# TriDeer.net
KiCad netlist of a schematic drawn in Altium Designer
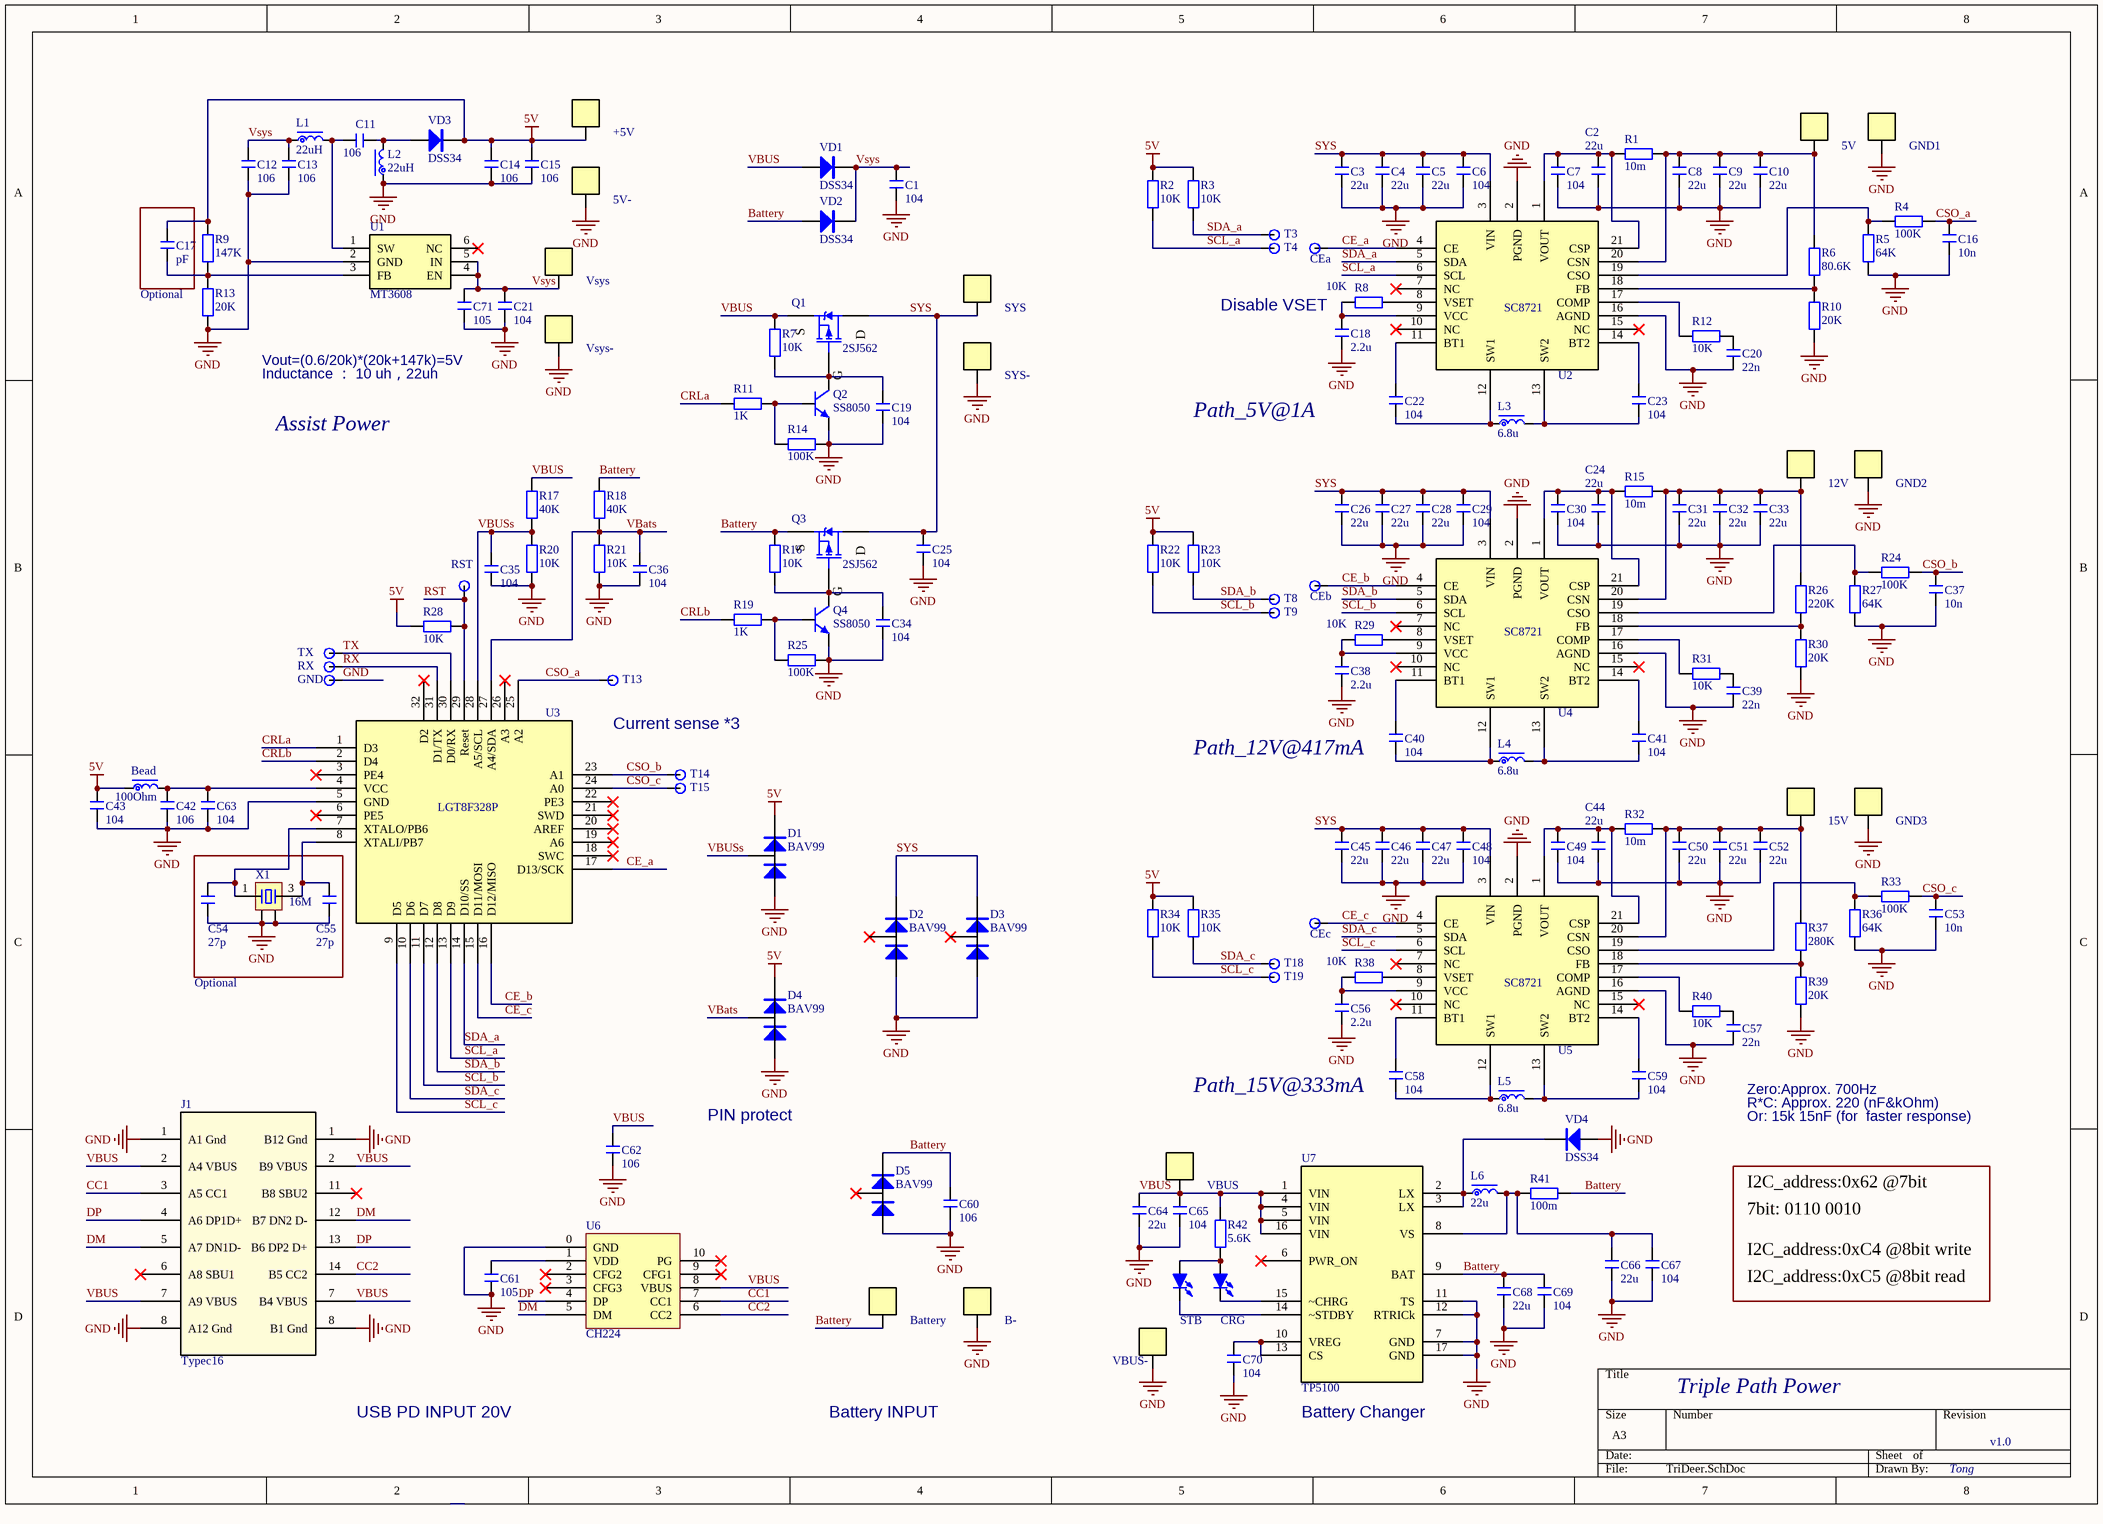
[diagram p0: TriDeer.SchDoc]

(export (version "E")
  (design (tool "Eeschema 10.0.6"))
  (components
    (comp (ref "+5V") (value "1") (footprint "connect") (libsource (lib "A") (part "connect")))
    (comp (ref "5V") (value "1") (footprint "connect") (libsource (lib "A") (part "connect")))
    (comp (ref "5V-") (value "1") (footprint "connect") (libsource (lib "A") (part "connect")))
    (comp (ref "12V") (value "1") (footprint "connect") (libsource (lib "A") (part "connect")))
    (comp (ref "15V") (value "1") (footprint "connect") (libsource (lib "A") (part "connect")))
    (comp (ref "B-") (value "1") (footprint "connect") (libsource (lib "A") (part "connect")))
    (comp (ref "Battery") (value "1") (footprint "connect") (libsource (lib "A") (part "connect")))
    (comp (ref "Bead")
      (value "100Ohm")
      (footprint "L 0805")
      (description "BEAD")
      (libsource (lib "A") (part "BEAD"))
    )
    (comp (ref "C1")
      (value "104")
      (footprint "C 0603")
      (description "瓷片电容-贴片")
      (libsource (lib "A") (part "Cap-CER-SMD_1"))
    )
    (comp (ref "C2")
      (value "22u")
      (footprint "C 0805")
      (description "瓷片电容-贴片")
      (libsource (lib "A") (part "Cap-CER-SMD_1"))
    )
    (comp (ref "C3")
      (value "22u")
      (footprint "C 0805")
      (description "瓷片电容-贴片")
      (libsource (lib "A") (part "Cap-CER-SMD_1"))
    )
    (comp (ref "C4")
      (value "22u")
      (footprint "C 0805")
      (description "瓷片电容-贴片")
      (libsource (lib "A") (part "Cap-CER-SMD_1"))
    )
    (comp (ref "C5")
      (value "22u")
      (footprint "C 0805")
      (description "瓷片电容-贴片")
      (libsource (lib "A") (part "Cap-CER-SMD_1"))
    )
    (comp (ref "C6")
      (value "104")
      (footprint "C 0603")
      (description "瓷片电容-贴片")
      (libsource (lib "A") (part "Cap-CER-SMD_1"))
    )
    (comp (ref "C7")
      (value "104")
      (footprint "C 0603")
      (description "瓷片电容-贴片")
      (libsource (lib "A") (part "Cap-CER-SMD_1"))
    )
    (comp (ref "C8")
      (value "22u")
      (footprint "C 0805")
      (description "瓷片电容-贴片")
      (libsource (lib "A") (part "Cap-CER-SMD_1"))
    )
    (comp (ref "C9")
      (value "22u")
      (footprint "C 0805")
      (description "瓷片电容-贴片")
      (libsource (lib "A") (part "Cap-CER-SMD_1"))
    )
    (comp (ref "C10")
      (value "22u")
      (footprint "C 0805")
      (description "瓷片电容-贴片")
      (libsource (lib "A") (part "Cap-CER-SMD_1"))
    )
    (comp (ref "C11")
      (value "106")
      (footprint "C 0805")
      (description "瓷片电容-贴片")
      (libsource (lib "A") (part "Cap-CER-SMD_1"))
    )
    (comp (ref "C12")
      (value "106")
      (footprint "C 0805")
      (description "瓷片电容-贴片")
      (libsource (lib "A") (part "Cap-CER-SMD_1"))
    )
    (comp (ref "C13")
      (value "106")
      (footprint "C 0805")
      (description "瓷片电容-贴片")
      (libsource (lib "A") (part "Cap-CER-SMD_1"))
    )
    (comp (ref "C14")
      (value "106")
      (footprint "C 0805")
      (description "瓷片电容-贴片")
      (libsource (lib "A") (part "Cap-CER-SMD_1"))
    )
    (comp (ref "C15")
      (value "106")
      (footprint "C 0805")
      (description "瓷片电容-贴片")
      (libsource (lib "A") (part "Cap-CER-SMD_1"))
    )
    (comp (ref "C16")
      (value "10n")
      (footprint "C 0603")
      (description "瓷片电容-贴片")
      (libsource (lib "A") (part "Cap-CER-SMD_1"))
    )
    (comp (ref "C17")
      (value "pF")
      (footprint "C 0603")
      (description "瓷片电容-贴片")
      (libsource (lib "A") (part "Cap-CER-SMD_1"))
    )
    (comp (ref "C18")
      (value "2.2u")
      (footprint "C 0603")
      (description "瓷片电容-贴片")
      (libsource (lib "A") (part "Cap-CER-SMD_1"))
    )
    (comp (ref "C19")
      (value "104")
      (footprint "C 0603")
      (description "瓷片电容-贴片")
      (libsource (lib "A") (part "Cap-CER-SMD_1"))
    )
    (comp (ref "C20")
      (value "22n")
      (footprint "C 0603")
      (description "瓷片电容-贴片")
      (libsource (lib "A") (part "Cap-CER-SMD_1"))
    )
    (comp (ref "C21")
      (value "104")
      (footprint "C 0603")
      (description "瓷片电容-贴片")
      (libsource (lib "A") (part "Cap-CER-SMD_1"))
    )
    (comp (ref "C22")
      (value "104")
      (footprint "C 0603")
      (description "瓷片电容-贴片")
      (libsource (lib "A") (part "Cap-CER-SMD_1"))
    )
    (comp (ref "C23")
      (value "104")
      (footprint "C 0603")
      (description "瓷片电容-贴片")
      (libsource (lib "A") (part "Cap-CER-SMD_1"))
    )
    (comp (ref "C24")
      (value "22u")
      (footprint "C 0805")
      (description "瓷片电容-贴片")
      (libsource (lib "A") (part "Cap-CER-SMD_1"))
    )
    (comp (ref "C25")
      (value "104")
      (footprint "C 0603")
      (description "瓷片电容-贴片")
      (libsource (lib "A") (part "Cap-CER-SMD_1"))
    )
    (comp (ref "C26")
      (value "22u")
      (footprint "C 0805")
      (description "瓷片电容-贴片")
      (libsource (lib "A") (part "Cap-CER-SMD_1"))
    )
    (comp (ref "C27")
      (value "22u")
      (footprint "C 0805")
      (description "瓷片电容-贴片")
      (libsource (lib "A") (part "Cap-CER-SMD_1"))
    )
    (comp (ref "C28")
      (value "22u")
      (footprint "C 0805")
      (description "瓷片电容-贴片")
      (libsource (lib "A") (part "Cap-CER-SMD_1"))
    )
    (comp (ref "C29")
      (value "104")
      (footprint "C 0603")
      (description "瓷片电容-贴片")
      (libsource (lib "A") (part "Cap-CER-SMD_1"))
    )
    (comp (ref "C30")
      (value "104")
      (footprint "C 0603")
      (description "瓷片电容-贴片")
      (libsource (lib "A") (part "Cap-CER-SMD_1"))
    )
    (comp (ref "C31")
      (value "22u")
      (footprint "C 0805")
      (description "瓷片电容-贴片")
      (libsource (lib "A") (part "Cap-CER-SMD_1"))
    )
    (comp (ref "C32")
      (value "22u")
      (footprint "C 0805")
      (description "瓷片电容-贴片")
      (libsource (lib "A") (part "Cap-CER-SMD_1"))
    )
    (comp (ref "C33")
      (value "22u")
      (footprint "C 0805")
      (description "瓷片电容-贴片")
      (libsource (lib "A") (part "Cap-CER-SMD_1"))
    )
    (comp (ref "C34")
      (value "104")
      (footprint "C 0603")
      (description "瓷片电容-贴片")
      (libsource (lib "A") (part "Cap-CER-SMD_1"))
    )
    (comp (ref "C35")
      (value "104")
      (footprint "C 0603")
      (description "瓷片电容-贴片")
      (libsource (lib "A") (part "Cap-CER-SMD_1"))
    )
    (comp (ref "C36")
      (value "104")
      (footprint "C 0603")
      (description "瓷片电容-贴片")
      (libsource (lib "A") (part "Cap-CER-SMD_1"))
    )
    (comp (ref "C37")
      (value "10n")
      (footprint "C 0603")
      (description "瓷片电容-贴片")
      (libsource (lib "A") (part "Cap-CER-SMD_1"))
    )
    (comp (ref "C38")
      (value "2.2u")
      (footprint "C 0603")
      (description "瓷片电容-贴片")
      (libsource (lib "A") (part "Cap-CER-SMD_1"))
    )
    (comp (ref "C39")
      (value "22n")
      (footprint "C 0603")
      (description "瓷片电容-贴片")
      (libsource (lib "A") (part "Cap-CER-SMD_1"))
    )
    (comp (ref "C40")
      (value "104")
      (footprint "C 0603")
      (description "瓷片电容-贴片")
      (libsource (lib "A") (part "Cap-CER-SMD_1"))
    )
    (comp (ref "C41")
      (value "104")
      (footprint "C 0603")
      (description "瓷片电容-贴片")
      (libsource (lib "A") (part "Cap-CER-SMD_1"))
    )
    (comp (ref "C42")
      (value "106")
      (footprint "C 0805")
      (description "瓷片电容-贴片")
      (libsource (lib "A") (part "Cap-CER-SMD_1"))
    )
    (comp (ref "C43")
      (value "104")
      (footprint "C 0603")
      (description "瓷片电容-贴片")
      (libsource (lib "A") (part "Cap-CER-SMD_1"))
    )
    (comp (ref "C44")
      (value "22u")
      (footprint "C 0805")
      (description "瓷片电容-贴片")
      (libsource (lib "A") (part "Cap-CER-SMD_1"))
    )
    (comp (ref "C45")
      (value "22u")
      (footprint "C 0805")
      (description "瓷片电容-贴片")
      (libsource (lib "A") (part "Cap-CER-SMD_1"))
    )
    (comp (ref "C46")
      (value "22u")
      (footprint "C 0805")
      (description "瓷片电容-贴片")
      (libsource (lib "A") (part "Cap-CER-SMD_1"))
    )
    (comp (ref "C47")
      (value "22u")
      (footprint "C 0805")
      (description "瓷片电容-贴片")
      (libsource (lib "A") (part "Cap-CER-SMD_1"))
    )
    (comp (ref "C48")
      (value "104")
      (footprint "C 0603")
      (description "瓷片电容-贴片")
      (libsource (lib "A") (part "Cap-CER-SMD_1"))
    )
    (comp (ref "C49")
      (value "104")
      (footprint "C 0603")
      (description "瓷片电容-贴片")
      (libsource (lib "A") (part "Cap-CER-SMD_1"))
    )
    (comp (ref "C50")
      (value "22u")
      (footprint "C 0805")
      (description "瓷片电容-贴片")
      (libsource (lib "A") (part "Cap-CER-SMD_1"))
    )
    (comp (ref "C51")
      (value "22u")
      (footprint "C 0805")
      (description "瓷片电容-贴片")
      (libsource (lib "A") (part "Cap-CER-SMD_1"))
    )
    (comp (ref "C52")
      (value "22u")
      (footprint "C 0805")
      (description "瓷片电容-贴片")
      (libsource (lib "A") (part "Cap-CER-SMD_1"))
    )
    (comp (ref "C53")
      (value "10n")
      (footprint "C 0603")
      (description "瓷片电容-贴片")
      (libsource (lib "A") (part "Cap-CER-SMD_1"))
    )
    (comp (ref "C54")
      (value "27p")
      (footprint "C 0603")
      (description "瓷片电容-贴片")
      (libsource (lib "A") (part "Cap-CER-SMD_1"))
    )
    (comp (ref "C55")
      (value "27p")
      (footprint "C 0603")
      (description "瓷片电容-贴片")
      (libsource (lib "A") (part "Cap-CER-SMD_1"))
    )
    (comp (ref "C56")
      (value "2.2u")
      (footprint "C 0603")
      (description "瓷片电容-贴片")
      (libsource (lib "A") (part "Cap-CER-SMD_1"))
    )
    (comp (ref "C57")
      (value "22n")
      (footprint "C 0603")
      (description "瓷片电容-贴片")
      (libsource (lib "A") (part "Cap-CER-SMD_1"))
    )
    (comp (ref "C58")
      (value "104")
      (footprint "C 0603")
      (description "瓷片电容-贴片")
      (libsource (lib "A") (part "Cap-CER-SMD_1"))
    )
    (comp (ref "C59")
      (value "104")
      (footprint "C 0603")
      (description "瓷片电容-贴片")
      (libsource (lib "A") (part "Cap-CER-SMD_1"))
    )
    (comp (ref "C60")
      (value "106")
      (footprint "C 0805")
      (description "瓷片电容-贴片")
      (libsource (lib "A") (part "Cap-CER-SMD_1"))
    )
    (comp (ref "C61")
      (value "105")
      (footprint "C 0603")
      (description "瓷片电容-贴片")
      (libsource (lib "A") (part "Cap-CER-SMD_1"))
    )
    (comp (ref "C62")
      (value "106")
      (footprint "C 0805")
      (description "瓷片电容-贴片")
      (libsource (lib "A") (part "Cap-CER-SMD_1"))
    )
    (comp (ref "C63")
      (value "104")
      (footprint "C 0603")
      (description "瓷片电容-贴片")
      (libsource (lib "A") (part "Cap-CER-SMD_1"))
    )
    (comp (ref "C64")
      (value "22u")
      (footprint "C 0805")
      (description "瓷片电容-贴片")
      (libsource (lib "A") (part "Cap-CER-SMD_1"))
    )
    (comp (ref "C65")
      (value "104")
      (footprint "C 0603")
      (description "瓷片电容-贴片")
      (libsource (lib "A") (part "Cap-CER-SMD_1"))
    )
    (comp (ref "C66")
      (value "22u")
      (footprint "C 0805")
      (description "瓷片电容-贴片")
      (libsource (lib "A") (part "Cap-CER-SMD_1"))
    )
    (comp (ref "C67")
      (value "104")
      (footprint "C 0603")
      (description "瓷片电容-贴片")
      (libsource (lib "A") (part "Cap-CER-SMD_1"))
    )
    (comp (ref "C68")
      (value "22u")
      (footprint "C 0805")
      (description "瓷片电容-贴片")
      (libsource (lib "A") (part "Cap-CER-SMD_1"))
    )
    (comp (ref "C69")
      (value "104")
      (footprint "C 0603")
      (description "瓷片电容-贴片")
      (libsource (lib "A") (part "Cap-CER-SMD_1"))
    )
    (comp (ref "C70")
      (value "104")
      (footprint "C 0603")
      (description "瓷片电容-贴片")
      (libsource (lib "A") (part "Cap-CER-SMD_1"))
    )
    (comp (ref "C71")
      (value "105")
      (footprint "C 0603")
      (description "瓷片电容-贴片")
      (libsource (lib "A") (part "Cap-CER-SMD_1"))
    )
    (comp (ref "CEa") (value "test") (footprint "TEST 1.6") (libsource (lib "A") (part "test")))
    (comp (ref "CEb") (value "test") (footprint "TEST 1.6") (libsource (lib "A") (part "test")))
    (comp (ref "CEc") (value "test") (footprint "TEST 1.6") (libsource (lib "A") (part "test")))
    (comp (ref "CRG")
      (value "红色")
      (footprint "LED 0603B")
      (description "贴片LED")
      (libsource (lib "A") (part "LED-SMD"))
    )
    (comp (ref "D1") (value "BAV99") (footprint "SOT23-3N") (libsource (lib "A") (part "BAV99")))
    (comp (ref "D2") (value "BAV99") (footprint "SOT23-3N") (libsource (lib "A") (part "BAV99")))
    (comp (ref "D3") (value "BAV99") (footprint "SOT23-3N") (libsource (lib "A") (part "BAV99")))
    (comp (ref "D4") (value "BAV99") (footprint "SOT23-3N") (libsource (lib "A") (part "BAV99")))
    (comp (ref "D5") (value "BAV99") (footprint "SOT23-3N") (libsource (lib "A") (part "BAV99")))
    (comp (ref "GND") (value "test") (footprint "TEST 1.6") (libsource (lib "A") (part "test")))
    (comp (ref "GND1") (value "1") (footprint "connect") (libsource (lib "A") (part "connect")))
    (comp (ref "GND2") (value "1") (footprint "connect") (libsource (lib "A") (part "connect")))
    (comp (ref "GND3") (value "1") (footprint "connect") (libsource (lib "A") (part "connect")))
    (comp (ref "J1") (value "Typec16") (footprint "typec 16p") (libsource (lib "A") (part "Typec16")))
    (comp (ref "L1")
      (value "22uH")
      (footprint "L252010")
      (description "贴片电感")
      (libsource (lib "A") (part "Ind-Beads-SMD"))
    )
    (comp (ref "L2")
      (value "22uH")
      (footprint "L252010")
      (description "贴片电感")
      (libsource (lib "") (part "Ind-Beads-SMD_1"))
    )
    (comp (ref "L3")
      (value "6.8u")
      (footprint "R0624")
      (description "贴片电感")
      (libsource (lib "A") (part "Ind-Beads-SMD"))
    )
    (comp (ref "L4")
      (value "6.8u")
      (footprint "R0624")
      (description "贴片电感")
      (libsource (lib "A") (part "Ind-Beads-SMD"))
    )
    (comp (ref "L5")
      (value "6.8u")
      (footprint "R0624")
      (description "贴片电感")
      (libsource (lib "A") (part "Ind-Beads-SMD"))
    )
    (comp (ref "L6")
      (value "22u")
      (footprint "R0624")
      (description "贴片电感")
      (libsource (lib "A") (part "Ind-Beads-SMD"))
    )
    (comp (ref "Q1")
      (value "2SJ562")
      (footprint "SOT89")
      (description "P沟道场效应管")
      (fields (field (name "版权归属") "源创客"))
      (libsource (lib "A") (part "2SJ562"))
    )
    (comp (ref "Q2")
      (value "SS8050")
      (footprint "SOT23-3N")
      (description "高频放大-NPN型")
      (fields (field (name "版权归属") "源创客"))
      (libsource (lib "A") (part "8050-SMD"))
    )
    (comp (ref "Q3")
      (value "2SJ562")
      (footprint "SOT89")
      (description "P沟道场效应管")
      (fields (field (name "版权归属") "源创客"))
      (libsource (lib "A") (part "2SJ562"))
    )
    (comp (ref "Q4")
      (value "SS8050")
      (footprint "SOT23-3N")
      (description "高频放大-NPN型")
      (fields (field (name "版权归属") "源创客"))
      (libsource (lib "A") (part "8050-SMD"))
    )
    (comp (ref "R1")
      (value "10m")
      (footprint "Res-SMD-0805")
      (description "固定电阻器-贴片")
      (libsource (lib "A") (part "Res-Fixed-SMD"))
    )
    (comp (ref "R2")
      (value "10K")
      (footprint "Res-SMD-0603")
      (description "固定电阻器-贴片")
      (libsource (lib "A") (part "Res-Fixed-SMD"))
    )
    (comp (ref "R3")
      (value "10K")
      (footprint "Res-SMD-0603")
      (description "固定电阻器-贴片")
      (libsource (lib "A") (part "Res-Fixed-SMD"))
    )
    (comp (ref "R4")
      (value "100K")
      (footprint "Res-SMD-0603")
      (description "固定电阻器-贴片")
      (libsource (lib "A") (part "Res-Fixed-SMD"))
    )
    (comp (ref "R5")
      (value "64K")
      (footprint "Res-SMD-0603")
      (description "固定电阻器-贴片")
      (libsource (lib "A") (part "Res-Fixed-SMD"))
    )
    (comp (ref "R6")
      (value "80.6K")
      (footprint "Res-SMD-0603")
      (description "固定电阻器-贴片")
      (libsource (lib "A") (part "Res-Fixed-SMD"))
    )
    (comp (ref "R7")
      (value "10K")
      (footprint "Res-SMD-0603")
      (description "固定电阻器-贴片")
      (libsource (lib "A") (part "Res-Fixed-SMD"))
    )
    (comp (ref "R8")
      (value "10K")
      (footprint "Res-SMD-0603")
      (description "固定电阻器-贴片")
      (libsource (lib "A") (part "Res-Fixed-SMD"))
    )
    (comp (ref "R9")
      (value "147K")
      (footprint "Res-SMD-0603")
      (description "固定电阻器-贴片")
      (libsource (lib "A") (part "Res-Fixed-SMD"))
    )
    (comp (ref "R10")
      (value "20K")
      (footprint "Res-SMD-0603")
      (description "固定电阻器-贴片")
      (libsource (lib "A") (part "Res-Fixed-SMD"))
    )
    (comp (ref "R11")
      (value "1K")
      (footprint "Res-SMD-0603")
      (description "固定电阻器-贴片")
      (libsource (lib "A") (part "Res-Fixed-SMD"))
    )
    (comp (ref "R12")
      (value "10K")
      (footprint "Res-SMD-0603")
      (description "固定电阻器-贴片")
      (libsource (lib "A") (part "Res-Fixed-SMD"))
    )
    (comp (ref "R13")
      (value "20K")
      (footprint "Res-SMD-0603")
      (description "固定电阻器-贴片")
      (libsource (lib "A") (part "Res-Fixed-SMD"))
    )
    (comp (ref "R14")
      (value "100K")
      (footprint "Res-SMD-0603")
      (description "固定电阻器-贴片")
      (libsource (lib "A") (part "Res-Fixed-SMD"))
    )
    (comp (ref "R15")
      (value "10m")
      (footprint "Res-SMD-0805")
      (description "固定电阻器-贴片")
      (libsource (lib "A") (part "Res-Fixed-SMD"))
    )
    (comp (ref "R16")
      (value "10K")
      (footprint "Res-SMD-0603")
      (description "固定电阻器-贴片")
      (libsource (lib "A") (part "Res-Fixed-SMD"))
    )
    (comp (ref "R17")
      (value "40K")
      (footprint "Res-SMD-0603")
      (description "固定电阻器-贴片")
      (libsource (lib "A") (part "Res-Fixed-SMD"))
    )
    (comp (ref "R18")
      (value "40K")
      (footprint "Res-SMD-0603")
      (description "固定电阻器-贴片")
      (libsource (lib "A") (part "Res-Fixed-SMD"))
    )
    (comp (ref "R19")
      (value "1K")
      (footprint "Res-SMD-0603")
      (description "固定电阻器-贴片")
      (libsource (lib "A") (part "Res-Fixed-SMD"))
    )
    (comp (ref "R20")
      (value "10K")
      (footprint "Res-SMD-0603")
      (description "固定电阻器-贴片")
      (libsource (lib "A") (part "Res-Fixed-SMD"))
    )
    (comp (ref "R21")
      (value "10K")
      (footprint "Res-SMD-0603")
      (description "固定电阻器-贴片")
      (libsource (lib "A") (part "Res-Fixed-SMD"))
    )
    (comp (ref "R22")
      (value "10K")
      (footprint "Res-SMD-0603")
      (description "固定电阻器-贴片")
      (libsource (lib "A") (part "Res-Fixed-SMD"))
    )
    (comp (ref "R23")
      (value "10K")
      (footprint "Res-SMD-0603")
      (description "固定电阻器-贴片")
      (libsource (lib "A") (part "Res-Fixed-SMD"))
    )
    (comp (ref "R24")
      (value "100K")
      (footprint "Res-SMD-0603")
      (description "固定电阻器-贴片")
      (libsource (lib "A") (part "Res-Fixed-SMD"))
    )
    (comp (ref "R25")
      (value "100K")
      (footprint "Res-SMD-0603")
      (description "固定电阻器-贴片")
      (libsource (lib "A") (part "Res-Fixed-SMD"))
    )
    (comp (ref "R26")
      (value "220K")
      (footprint "Res-SMD-0603")
      (description "固定电阻器-贴片")
      (libsource (lib "A") (part "Res-Fixed-SMD"))
    )
    (comp (ref "R27")
      (value "64K")
      (footprint "Res-SMD-0603")
      (description "固定电阻器-贴片")
      (libsource (lib "A") (part "Res-Fixed-SMD"))
    )
    (comp (ref "R28")
      (value "10K")
      (footprint "Res-SMD-0603")
      (description "固定电阻器-贴片")
      (libsource (lib "A") (part "Res-Fixed-SMD"))
    )
    (comp (ref "R29")
      (value "10K")
      (footprint "Res-SMD-0603")
      (description "固定电阻器-贴片")
      (libsource (lib "A") (part "Res-Fixed-SMD"))
    )
    (comp (ref "R30")
      (value "20K")
      (footprint "Res-SMD-0603")
      (description "固定电阻器-贴片")
      (libsource (lib "A") (part "Res-Fixed-SMD"))
    )
    (comp (ref "R31")
      (value "10K")
      (footprint "Res-SMD-0603")
      (description "固定电阻器-贴片")
      (libsource (lib "A") (part "Res-Fixed-SMD"))
    )
    (comp (ref "R32")
      (value "10m")
      (footprint "Res-SMD-0805")
      (description "固定电阻器-贴片")
      (libsource (lib "A") (part "Res-Fixed-SMD"))
    )
    (comp (ref "R33")
      (value "100K")
      (footprint "Res-SMD-0603")
      (description "固定电阻器-贴片")
      (libsource (lib "A") (part "Res-Fixed-SMD"))
    )
    (comp (ref "R34")
      (value "10K")
      (footprint "Res-SMD-0603")
      (description "固定电阻器-贴片")
      (libsource (lib "A") (part "Res-Fixed-SMD"))
    )
    (comp (ref "R35")
      (value "10K")
      (footprint "Res-SMD-0603")
      (description "固定电阻器-贴片")
      (libsource (lib "A") (part "Res-Fixed-SMD"))
    )
    (comp (ref "R36")
      (value "64K")
      (footprint "Res-SMD-0603")
      (description "固定电阻器-贴片")
      (libsource (lib "A") (part "Res-Fixed-SMD"))
    )
    (comp (ref "R37")
      (value "280K")
      (footprint "Res-SMD-0603")
      (description "固定电阻器-贴片")
      (libsource (lib "A") (part "Res-Fixed-SMD"))
    )
    (comp (ref "R38")
      (value "10K")
      (footprint "Res-SMD-0603")
      (description "固定电阻器-贴片")
      (libsource (lib "A") (part "Res-Fixed-SMD"))
    )
    (comp (ref "R39")
      (value "20K")
      (footprint "Res-SMD-0603")
      (description "固定电阻器-贴片")
      (libsource (lib "A") (part "Res-Fixed-SMD"))
    )
    (comp (ref "R40")
      (value "10K")
      (footprint "Res-SMD-0603")
      (description "固定电阻器-贴片")
      (libsource (lib "A") (part "Res-Fixed-SMD"))
    )
    (comp (ref "R41")
      (value "100m")
      (footprint "Res-SMD-1206")
      (description "固定电阻器-贴片")
      (libsource (lib "A") (part "Res-Fixed-SMD"))
    )
    (comp (ref "R42")
      (value "5.6K")
      (footprint "Res-SMD-0603")
      (description "固定电阻器-贴片")
      (libsource (lib "A") (part "Res-Fixed-SMD"))
    )
    (comp (ref "RST") (value "test") (footprint "TEST 1.6") (libsource (lib "A") (part "test")))
    (comp (ref "RX") (value "test") (footprint "TEST 1.6") (libsource (lib "A") (part "test")))
    (comp (ref "STB")
      (value "红色")
      (footprint "LED 0603B")
      (description "贴片LED")
      (libsource (lib "A") (part "LED-SMD"))
    )
    (comp (ref "SYS") (value "1") (footprint "connect") (libsource (lib "A") (part "connect")))
    (comp (ref "SYS-") (value "1") (footprint "connect") (libsource (lib "A") (part "connect")))
    (comp (ref "T3") (value "test") (footprint "TEST 1.6") (libsource (lib "A") (part "test")))
    (comp (ref "T4") (value "test") (footprint "TEST 1.6") (libsource (lib "A") (part "test")))
    (comp (ref "T8") (value "test") (footprint "TEST 1.6") (libsource (lib "A") (part "test")))
    (comp (ref "T9") (value "test") (footprint "TEST 1.6") (libsource (lib "A") (part "test")))
    (comp (ref "T13") (value "test") (footprint "TEST 1.6") (libsource (lib "A") (part "test")))
    (comp (ref "T14") (value "test") (footprint "TEST 1.6") (libsource (lib "A") (part "test")))
    (comp (ref "T15") (value "test") (footprint "TEST 1.6") (libsource (lib "A") (part "test")))
    (comp (ref "T18") (value "test") (footprint "TEST 1.6") (libsource (lib "A") (part "test")))
    (comp (ref "T19") (value "test") (footprint "TEST 1.6") (libsource (lib "A") (part "test")))
    (comp (ref "TX") (value "test") (footprint "TEST 1.6") (libsource (lib "A") (part "test")))
    (comp (ref "U1") (value "MT3608") (footprint "SOT23-6N") (libsource (lib "A") (part "MT3608")))
    (comp (ref "U2")
      (value "SC8721")
      (footprint "QFN-21_L4.0-W4.0-P0.40-BL_SC8721QFER")
      (libsource (lib "A") (part "SC8721"))
    )
    (comp (ref "U3") (value "LGT8F328P") (footprint "TQFP32 7x7_N") (libsource (lib "A") (part "LGT8F328P")))
    (comp (ref "U4")
      (value "SC8721")
      (footprint "QFN-21_L4.0-W4.0-P0.40-BL_SC8721QFER")
      (libsource (lib "A") (part "SC8721"))
    )
    (comp (ref "U5")
      (value "SC8721")
      (footprint "QFN-21_L4.0-W4.0-P0.40-BL_SC8721QFER")
      (libsource (lib "A") (part "SC8721"))
    )
    (comp (ref "U6") (value "CH224") (footprint "SOP10_N") (libsource (lib "A") (part "CH224")))
    (comp (ref "U7")
      (value "TP5100")
      (footprint "TQFN-16_L4.0-W4.0-P0.65-BL-EP")
      (libsource (lib "A") (part "TP5100"))
    )
    (comp (ref "VBUS") (value "1") (footprint "connect") (libsource (lib "A") (part "connect")))
    (comp (ref "VBUS-") (value "1") (footprint "connect") (libsource (lib "A") (part "connect")))
    (comp (ref "VD1")
      (value "DSS34")
      (footprint "SOD-123F")
      (description "肖特基二极管")
      (fields (field (name "版权归属") "源创客"))
      (libsource (lib "A") (part "DSS34"))
    )
    (comp (ref "VD2")
      (value "DSS34")
      (footprint "SOD-123F")
      (description "肖特基二极管")
      (fields (field (name "版权归属") "源创客"))
      (libsource (lib "A") (part "DSS34"))
    )
    (comp (ref "VD3")
      (value "DSS34")
      (footprint "SOD-123F")
      (description "肖特基二极管")
      (fields (field (name "版权归属") "源创客"))
      (libsource (lib "A") (part "DSS34"))
    )
    (comp (ref "VD4")
      (value "DSS34")
      (footprint "SOD-123F")
      (description "肖特基二极管")
      (fields (field (name "版权归属") "源创客"))
      (libsource (lib "A") (part "DSS34"))
    )
    (comp (ref "Vsys") (value "1") (footprint "connect") (libsource (lib "A") (part "connect")))
    (comp (ref "Vsys-") (value "1") (footprint "connect") (libsource (lib "A") (part "connect")))
    (comp (ref "X1")
      (value "16M")
      (footprint "XTAL-3225")
      (description "4脚晶振")
      (libsource (lib "A") (part "XTAL-4"))
    )
  )
  (nets
    (net (code "1") (name "/Battery") (class "Default")
      (node (ref "Battery") (pin "1") (pinfunction "1_1") (pintype "passive"))
      (node (ref "C60") (pin "2") (pinfunction "2_2") (pintype "passive"))
      (node (ref "C68") (pin "1") (pinfunction "1_1") (pintype "passive"))
      (node (ref "C69") (pin "1") (pinfunction "1_1") (pintype "passive"))
      (node (ref "D5") (pin "2") (pintype "passive"))
      (node (ref "Q3") (pin "3") (pinfunction "S_3") (pintype "passive"))
      (node (ref "R16") (pin "1") (pinfunction "1_1") (pintype "passive"))
      (node (ref "R18") (pin "1") (pinfunction "1_1") (pintype "passive"))
      (node (ref "R41") (pin "2") (pinfunction "2_2") (pintype "passive"))
      (node (ref "U7") (pin "9") (pinfunction "BAT_9") (pintype "passive"))
      (node (ref "VD2") (pin "1") (pinfunction "A_1") (pintype "passive"))
    )
    (net (code "2") (name "/CC1") (class "Default")
      (node (ref "J1") (pin "3") (pinfunction "A5_CC1_3") (pintype "passive"))
      (node (ref "U6") (pin "7") (pinfunction "CC1_7") (pintype "passive"))
    )
    (net (code "3") (name "/CC2") (class "Default")
      (node (ref "J1") (pin "14") (pinfunction "B5_CC2_14") (pintype "passive"))
      (node (ref "U6") (pin "6") (pinfunction "CC2_6") (pintype "passive"))
    )
    (net (code "4") (name "/CE_a") (class "Default")
      (node (ref "CEa") (pin "1") (pinfunction "1_1") (pintype "passive"))
      (node (ref "U2") (pin "4") (pinfunction "CE_4") (pintype "passive"))
      (node (ref "U3") (pin "17") (pinfunction "D13/SCK_17") (pintype "passive"))
    )
    (net (code "5") (name "/CE_b") (class "Default")
      (node (ref "CEb") (pin "1") (pinfunction "1_1") (pintype "passive"))
      (node (ref "U3") (pin "16") (pinfunction "D12/MISO_16") (pintype "passive"))
      (node (ref "U4") (pin "4") (pinfunction "CE_4") (pintype "passive"))
    )
    (net (code "6") (name "/CE_c") (class "Default")
      (node (ref "CEc") (pin "1") (pinfunction "1_1") (pintype "passive"))
      (node (ref "U3") (pin "15") (pinfunction "D11/MOSI_15") (pintype "passive"))
      (node (ref "U5") (pin "4") (pinfunction "CE_4") (pintype "passive"))
    )
    (net (code "7") (name "/CRLa") (class "Default")
      (node (ref "R11") (pin "2") (pinfunction "2_2") (pintype "passive"))
      (node (ref "U3") (pin "1") (pinfunction "D3_1") (pintype "passive"))
    )
    (net (code "8") (name "/CRLb") (class "Default")
      (node (ref "R19") (pin "2") (pinfunction "2_2") (pintype "passive"))
      (node (ref "U3") (pin "2") (pinfunction "D4_2") (pintype "passive"))
    )
    (net (code "9") (name "/CSO_a") (class "Default")
      (node (ref "C16") (pin "1") (pinfunction "1_1") (pintype "passive"))
      (node (ref "R4") (pin "1") (pinfunction "1_1") (pintype "passive"))
      (node (ref "T13") (pin "1") (pinfunction "1_1") (pintype "passive"))
      (node (ref "U3") (pin "25") (pinfunction "A2_25") (pintype "passive"))
    )
    (net (code "10") (name "/CSO_b") (class "Default")
      (node (ref "C37") (pin "1") (pinfunction "1_1") (pintype "passive"))
      (node (ref "R24") (pin "1") (pinfunction "1_1") (pintype "passive"))
      (node (ref "T14") (pin "1") (pinfunction "1_1") (pintype "passive"))
      (node (ref "U3") (pin "23") (pinfunction "A1_23") (pintype "passive"))
    )
    (net (code "11") (name "/CSO_c") (class "Default")
      (node (ref "C53") (pin "1") (pinfunction "1_1") (pintype "passive"))
      (node (ref "R33") (pin "1") (pinfunction "1_1") (pintype "passive"))
      (node (ref "T15") (pin "1") (pinfunction "1_1") (pintype "passive"))
      (node (ref "U3") (pin "24") (pinfunction "A0_24") (pintype "passive"))
    )
    (net (code "12") (name "/DM") (class "Default")
      (node (ref "J1") (pin "12") (pinfunction "B7_DN2_D-_12") (pintype "passive"))
      (node (ref "J1") (pin "5") (pinfunction "A7_DN1D-_5") (pintype "passive"))
      (node (ref "U6") (pin "5") (pinfunction "DM_5") (pintype "passive"))
    )
    (net (code "13") (name "/DP") (class "Default")
      (node (ref "J1") (pin "13") (pinfunction "B6_DP2_D+_13") (pintype "passive"))
      (node (ref "J1") (pin "4") (pinfunction "A6_DP1D+_4") (pintype "passive"))
      (node (ref "U6") (pin "4") (pinfunction "DP_4") (pintype "passive"))
    )
    (net (code "14") (name "/RST") (class "Default")
      (node (ref "R28") (pin "2") (pinfunction "2_2") (pintype "passive"))
      (node (ref "RST") (pin "1") (pinfunction "1_1") (pintype "passive"))
      (node (ref "U3") (pin "29") (pinfunction "Reset_29") (pintype "passive"))
    )
    (net (code "15") (name "/RX") (class "Default")
      (node (ref "RX") (pin "1") (pinfunction "1_1") (pintype "passive"))
      (node (ref "U3") (pin "31") (pinfunction "D1/TX_31") (pintype "passive"))
    )
    (net (code "16") (name "/SCL_a") (class "Default")
      (node (ref "R2") (pin "2") (pinfunction "2_2") (pintype "passive"))
      (node (ref "T4") (pin "1") (pinfunction "1_1") (pintype "passive"))
      (node (ref "U2") (pin "6") (pinfunction "SCL_6") (pintype "passive"))
      (node (ref "U3") (pin "13") (pinfunction "D9_13") (pintype "passive"))
    )
    (net (code "17") (name "/SCL_b") (class "Default")
      (node (ref "R22") (pin "2") (pinfunction "2_2") (pintype "passive"))
      (node (ref "T9") (pin "1") (pinfunction "1_1") (pintype "passive"))
      (node (ref "U3") (pin "11") (pinfunction "D7_11") (pintype "passive"))
      (node (ref "U4") (pin "6") (pinfunction "SCL_6") (pintype "passive"))
    )
    (net (code "18") (name "/SCL_c") (class "Default")
      (node (ref "R34") (pin "2") (pinfunction "2_2") (pintype "passive"))
      (node (ref "T19") (pin "1") (pinfunction "1_1") (pintype "passive"))
      (node (ref "U3") (pin "9") (pinfunction "D5_9") (pintype "passive"))
      (node (ref "U5") (pin "6") (pinfunction "SCL_6") (pintype "passive"))
    )
    (net (code "19") (name "/SDA_a") (class "Default")
      (node (ref "R3") (pin "2") (pinfunction "2_2") (pintype "passive"))
      (node (ref "T3") (pin "1") (pinfunction "1_1") (pintype "passive"))
      (node (ref "U2") (pin "5") (pinfunction "SDA_5") (pintype "passive"))
      (node (ref "U3") (pin "14") (pinfunction "D10/SS_14") (pintype "passive"))
    )
    (net (code "20") (name "/SDA_b") (class "Default")
      (node (ref "R23") (pin "2") (pinfunction "2_2") (pintype "passive"))
      (node (ref "T8") (pin "1") (pinfunction "1_1") (pintype "passive"))
      (node (ref "U3") (pin "12") (pinfunction "D8_12") (pintype "passive"))
      (node (ref "U4") (pin "5") (pinfunction "SDA_5") (pintype "passive"))
    )
    (net (code "21") (name "/SDA_c") (class "Default")
      (node (ref "R35") (pin "2") (pinfunction "2_2") (pintype "passive"))
      (node (ref "T18") (pin "1") (pinfunction "1_1") (pintype "passive"))
      (node (ref "U3") (pin "10") (pinfunction "D6_10") (pintype "passive"))
      (node (ref "U5") (pin "5") (pinfunction "SDA_5") (pintype "passive"))
    )
    (net (code "22") (name "/SYS") (class "Default")
      (node (ref "C25") (pin "1") (pinfunction "1_1") (pintype "passive"))
      (node (ref "C26") (pin "1") (pinfunction "1_1") (pintype "passive"))
      (node (ref "C27") (pin "1") (pinfunction "1_1") (pintype "passive"))
      (node (ref "C28") (pin "1") (pinfunction "1_1") (pintype "passive"))
      (node (ref "C29") (pin "1") (pinfunction "1_1") (pintype "passive"))
      (node (ref "C3") (pin "1") (pinfunction "1_1") (pintype "passive"))
      (node (ref "C4") (pin "1") (pinfunction "1_1") (pintype "passive"))
      (node (ref "C45") (pin "1") (pinfunction "1_1") (pintype "passive"))
      (node (ref "C46") (pin "1") (pinfunction "1_1") (pintype "passive"))
      (node (ref "C47") (pin "1") (pinfunction "1_1") (pintype "passive"))
      (node (ref "C48") (pin "1") (pinfunction "1_1") (pintype "passive"))
      (node (ref "C5") (pin "1") (pinfunction "1_1") (pintype "passive"))
      (node (ref "C6") (pin "1") (pinfunction "1_1") (pintype "passive"))
      (node (ref "D2") (pin "2") (pintype "passive"))
      (node (ref "D3") (pin "2") (pintype "passive"))
      (node (ref "Q1") (pin "2") (pinfunction "D_2") (pintype "passive"))
      (node (ref "Q3") (pin "2") (pinfunction "D_2") (pintype "passive"))
      (node (ref "SYS") (pin "1") (pinfunction "1_1") (pintype "passive"))
      (node (ref "U2") (pin "3") (pinfunction "VIN_3") (pintype "passive"))
      (node (ref "U4") (pin "3") (pinfunction "VIN_3") (pintype "passive"))
      (node (ref "U5") (pin "3") (pinfunction "VIN_3") (pintype "passive"))
    )
    (net (code "23") (name "/TX") (class "Default")
      (node (ref "TX") (pin "1") (pinfunction "1_1") (pintype "passive"))
      (node (ref "U3") (pin "30") (pinfunction "D0/RX_30") (pintype "passive"))
    )
    (net (code "24") (name "/VBUS") (class "Default")
      (node (ref "C62") (pin "2") (pinfunction "2_2") (pintype "passive"))
      (node (ref "C64") (pin "1") (pinfunction "1_1") (pintype "passive"))
      (node (ref "C65") (pin "1") (pinfunction "1_1") (pintype "passive"))
      (node (ref "J1") (pin "2") (pinfunction "B9_VBUS_2") (pintype "passive"))
      (node (ref "J1") (pin "7") (pinfunction "B4_VBUS_7") (pintype "passive"))
      (node (ref "Q1") (pin "3") (pinfunction "S_3") (pintype "passive"))
      (node (ref "R17") (pin "1") (pinfunction "1_1") (pintype "passive"))
      (node (ref "R42") (pin "1") (pinfunction "1_1") (pintype "passive"))
      (node (ref "R7") (pin "1") (pinfunction "1_1") (pintype "passive"))
      (node (ref "U6") (pin "8") (pinfunction "VBUS_8") (pintype "passive"))
      (node (ref "U7") (pin "1") (pinfunction "VIN_1") (pintype "passive"))
      (node (ref "U7") (pin "16") (pinfunction "VIN_16") (pintype "passive"))
      (node (ref "U7") (pin "4") (pinfunction "VIN_4") (pintype "passive"))
      (node (ref "U7") (pin "5") (pinfunction "VIN_5") (pintype "passive"))
      (node (ref "VBUS") (pin "1") (pinfunction "1_1") (pintype "passive"))
      (node (ref "VD1") (pin "1") (pinfunction "A_1") (pintype "passive"))
    )
    (net (code "25") (name "/VBUSs") (class "Default")
      (node (ref "C35") (pin "2") (pinfunction "2_2") (pintype "passive"))
      (node (ref "D1") (pin "3") (pintype "passive"))
      (node (ref "R17") (pin "2") (pinfunction "2_2") (pintype "passive"))
      (node (ref "R20") (pin "1") (pinfunction "1_1") (pintype "passive"))
      (node (ref "U3") (pin "28") (pinfunction "A5/SCL_28") (pintype "passive"))
    )
    (net (code "26") (name "/VBats") (class "Default")
      (node (ref "C36") (pin "2") (pinfunction "2_2") (pintype "passive"))
      (node (ref "D4") (pin "3") (pintype "passive"))
      (node (ref "R18") (pin "2") (pinfunction "2_2") (pintype "passive"))
      (node (ref "R21") (pin "1") (pinfunction "1_1") (pintype "passive"))
      (node (ref "U3") (pin "27") (pinfunction "A4/SDA_27") (pintype "passive"))
    )
    (net (code "27") (name "/Vsys") (class "Default")
      (node (ref "C1") (pin "1") (pinfunction "1_1") (pintype "passive"))
      (node (ref "C12") (pin "2") (pinfunction "2_2") (pintype "passive"))
      (node (ref "C13") (pin "2") (pinfunction "2_2") (pintype "passive"))
      (node (ref "C21") (pin "1") (pinfunction "1_1") (pintype "passive"))
      (node (ref "C71") (pin "1") (pinfunction "1_1") (pintype "passive"))
      (node (ref "L1") (pin "1") (pinfunction "1_1") (pintype "passive"))
      (node (ref "U1") (pin "4") (pinfunction "EN_4") (pintype "passive"))
      (node (ref "U1") (pin "5") (pinfunction "IN_5") (pintype "passive"))
      (node (ref "VD1") (pin "2") (pinfunction "K_2") (pintype "passive"))
      (node (ref "VD2") (pin "2") (pinfunction "K_2") (pintype "passive"))
      (node (ref "Vsys") (pin "1") (pinfunction "1_1") (pintype "passive"))
    )
    (net (code "28") (name "5V") (class "Default")
      (node (ref "+5V") (pin "1") (pinfunction "1_1") (pintype "passive"))
      (node (ref "Bead") (pin "1") (pinfunction "1_1") (pintype "passive"))
      (node (ref "C14") (pin "2") (pinfunction "2_2") (pintype "passive"))
      (node (ref "C15") (pin "2") (pinfunction "2_2") (pintype "passive"))
      (node (ref "C17") (pin "2") (pinfunction "2_2") (pintype "passive"))
      (node (ref "C43") (pin "1") (pinfunction "1_1") (pintype "passive"))
      (node (ref "D1") (pin "2") (pintype "passive"))
      (node (ref "D4") (pin "2") (pintype "passive"))
      (node (ref "R2") (pin "1") (pinfunction "1_1") (pintype "passive"))
      (node (ref "R22") (pin "1") (pinfunction "1_1") (pintype "passive"))
      (node (ref "R23") (pin "1") (pinfunction "1_1") (pintype "passive"))
      (node (ref "R28") (pin "1") (pinfunction "1_1") (pintype "passive"))
      (node (ref "R3") (pin "1") (pinfunction "1_1") (pintype "passive"))
      (node (ref "R34") (pin "1") (pinfunction "1_1") (pintype "passive"))
      (node (ref "R35") (pin "1") (pinfunction "1_1") (pintype "passive"))
      (node (ref "R9") (pin "2") (pinfunction "2_2") (pintype "passive"))
      (node (ref "VD3") (pin "2") (pinfunction "K_2") (pintype "passive"))
    )
    (net (code "29") (name "GND") (class "Default")
      (node (ref "5V-") (pin "1") (pinfunction "1_1") (pintype "passive"))
      (node (ref "B-") (pin "1") (pinfunction "1_1") (pintype "passive"))
      (node (ref "C1") (pin "2") (pinfunction "2_2") (pintype "passive"))
      (node (ref "C10") (pin "2") (pinfunction "2_2") (pintype "passive"))
      (node (ref "C12") (pin "1") (pinfunction "1_1") (pintype "passive"))
      (node (ref "C13") (pin "1") (pinfunction "1_1") (pintype "passive"))
      (node (ref "C14") (pin "1") (pinfunction "1_1") (pintype "passive"))
      (node (ref "C15") (pin "1") (pinfunction "1_1") (pintype "passive"))
      (node (ref "C16") (pin "2") (pinfunction "2_2") (pintype "passive"))
      (node (ref "C18") (pin "2") (pinfunction "2_2") (pintype "passive"))
      (node (ref "C19") (pin "1") (pinfunction "1_1") (pintype "passive"))
      (node (ref "C2") (pin "2") (pinfunction "2_2") (pintype "passive"))
      (node (ref "C20") (pin "1") (pinfunction "1_1") (pintype "passive"))
      (node (ref "C21") (pin "2") (pinfunction "2_2") (pintype "passive"))
      (node (ref "C24") (pin "2") (pinfunction "2_2") (pintype "passive"))
      (node (ref "C25") (pin "2") (pinfunction "2_2") (pintype "passive"))
      (node (ref "C26") (pin "2") (pinfunction "2_2") (pintype "passive"))
      (node (ref "C27") (pin "2") (pinfunction "2_2") (pintype "passive"))
      (node (ref "C28") (pin "2") (pinfunction "2_2") (pintype "passive"))
      (node (ref "C29") (pin "2") (pinfunction "2_2") (pintype "passive"))
      (node (ref "C3") (pin "2") (pinfunction "2_2") (pintype "passive"))
      (node (ref "C30") (pin "2") (pinfunction "2_2") (pintype "passive"))
      (node (ref "C31") (pin "2") (pinfunction "2_2") (pintype "passive"))
      (node (ref "C32") (pin "2") (pinfunction "2_2") (pintype "passive"))
      (node (ref "C33") (pin "2") (pinfunction "2_2") (pintype "passive"))
      (node (ref "C34") (pin "1") (pinfunction "1_1") (pintype "passive"))
      (node (ref "C35") (pin "1") (pinfunction "1_1") (pintype "passive"))
      (node (ref "C36") (pin "1") (pinfunction "1_1") (pintype "passive"))
      (node (ref "C37") (pin "2") (pinfunction "2_2") (pintype "passive"))
      (node (ref "C38") (pin "2") (pinfunction "2_2") (pintype "passive"))
      (node (ref "C39") (pin "1") (pinfunction "1_1") (pintype "passive"))
      (node (ref "C4") (pin "2") (pinfunction "2_2") (pintype "passive"))
      (node (ref "C42") (pin "2") (pinfunction "2_2") (pintype "passive"))
      (node (ref "C43") (pin "2") (pinfunction "2_2") (pintype "passive"))
      (node (ref "C44") (pin "2") (pinfunction "2_2") (pintype "passive"))
      (node (ref "C45") (pin "2") (pinfunction "2_2") (pintype "passive"))
      (node (ref "C46") (pin "2") (pinfunction "2_2") (pintype "passive"))
      (node (ref "C47") (pin "2") (pinfunction "2_2") (pintype "passive"))
      (node (ref "C48") (pin "2") (pinfunction "2_2") (pintype "passive"))
      (node (ref "C49") (pin "2") (pinfunction "2_2") (pintype "passive"))
      (node (ref "C5") (pin "2") (pinfunction "2_2") (pintype "passive"))
      (node (ref "C50") (pin "2") (pinfunction "2_2") (pintype "passive"))
      (node (ref "C51") (pin "2") (pinfunction "2_2") (pintype "passive"))
      (node (ref "C52") (pin "2") (pinfunction "2_2") (pintype "passive"))
      (node (ref "C53") (pin "2") (pinfunction "2_2") (pintype "passive"))
      (node (ref "C54") (pin "2") (pinfunction "2_2") (pintype "passive"))
      (node (ref "C55") (pin "2") (pinfunction "2_2") (pintype "passive"))
      (node (ref "C56") (pin "2") (pinfunction "2_2") (pintype "passive"))
      (node (ref "C57") (pin "1") (pinfunction "1_1") (pintype "passive"))
      (node (ref "C6") (pin "2") (pinfunction "2_2") (pintype "passive"))
      (node (ref "C60") (pin "1") (pinfunction "1_1") (pintype "passive"))
      (node (ref "C61") (pin "2") (pinfunction "2_2") (pintype "passive"))
      (node (ref "C62") (pin "1") (pinfunction "1_1") (pintype "passive"))
      (node (ref "C63") (pin "2") (pinfunction "2_2") (pintype "passive"))
      (node (ref "C64") (pin "2") (pinfunction "2_2") (pintype "passive"))
      (node (ref "C65") (pin "2") (pinfunction "2_2") (pintype "passive"))
      (node (ref "C66") (pin "2") (pinfunction "2_2") (pintype "passive"))
      (node (ref "C67") (pin "2") (pinfunction "2_2") (pintype "passive"))
      (node (ref "C68") (pin "2") (pinfunction "2_2") (pintype "passive"))
      (node (ref "C69") (pin "2") (pinfunction "2_2") (pintype "passive"))
      (node (ref "C7") (pin "2") (pinfunction "2_2") (pintype "passive"))
      (node (ref "C70") (pin "2") (pinfunction "2_2") (pintype "passive"))
      (node (ref "C71") (pin "2") (pinfunction "2_2") (pintype "passive"))
      (node (ref "C8") (pin "2") (pinfunction "2_2") (pintype "passive"))
      (node (ref "C9") (pin "2") (pinfunction "2_2") (pintype "passive"))
      (node (ref "D1") (pin "1") (pintype "passive"))
      (node (ref "D2") (pin "1") (pintype "passive"))
      (node (ref "D3") (pin "1") (pintype "passive"))
      (node (ref "D4") (pin "1") (pintype "passive"))
      (node (ref "D5") (pin "1") (pintype "passive"))
      (node (ref "GND") (pin "1") (pinfunction "1_1") (pintype "passive"))
      (node (ref "GND1") (pin "1") (pinfunction "1_1") (pintype "passive"))
      (node (ref "GND2") (pin "1") (pinfunction "1_1") (pintype "passive"))
      (node (ref "GND3") (pin "1") (pinfunction "1_1") (pintype "passive"))
      (node (ref "J1") (pin "1") (pinfunction "A1_Gnd_1") (pintype "passive"))
      (node (ref "J1") (pin "8") (pinfunction "A12_Gnd_8") (pintype "passive"))
      (node (ref "L2") (pin "1") (pinfunction "1_1") (pintype "passive"))
      (node (ref "Q2") (pin "2") (pinfunction "E_2") (pintype "passive"))
      (node (ref "Q4") (pin "2") (pinfunction "E_2") (pintype "passive"))
      (node (ref "R10") (pin "2") (pinfunction "2_2") (pintype "passive"))
      (node (ref "R13") (pin "1") (pinfunction "1_1") (pintype "passive"))
      (node (ref "R14") (pin "1") (pinfunction "1_1") (pintype "passive"))
      (node (ref "R20") (pin "2") (pinfunction "2_2") (pintype "passive"))
      (node (ref "R21") (pin "2") (pinfunction "2_2") (pintype "passive"))
      (node (ref "R25") (pin "1") (pinfunction "1_1") (pintype "passive"))
      (node (ref "R27") (pin "2") (pinfunction "2_2") (pintype "passive"))
      (node (ref "R30") (pin "2") (pinfunction "2_2") (pintype "passive"))
      (node (ref "R36") (pin "2") (pinfunction "2_2") (pintype "passive"))
      (node (ref "R39") (pin "2") (pinfunction "2_2") (pintype "passive"))
      (node (ref "R5") (pin "2") (pinfunction "2_2") (pintype "passive"))
      (node (ref "SYS-") (pin "1") (pinfunction "1_1") (pintype "passive"))
      (node (ref "U1") (pin "2") (pinfunction "GND_2") (pintype "passive"))
      (node (ref "U2") (pin "16") (pinfunction "AGND_16") (pintype "passive"))
      (node (ref "U2") (pin "2") (pinfunction "PGND_2") (pintype "passive"))
      (node (ref "U3") (pin "5") (pinfunction "GND_5") (pintype "passive"))
      (node (ref "U4") (pin "16") (pinfunction "AGND_16") (pintype "passive"))
      (node (ref "U4") (pin "2") (pinfunction "PGND_2") (pintype "passive"))
      (node (ref "U5") (pin "16") (pinfunction "AGND_16") (pintype "passive"))
      (node (ref "U5") (pin "2") (pinfunction "PGND_2") (pintype "passive"))
      (node (ref "U6") (pin "0") (pinfunction "GND_0") (pintype "passive"))
      (node (ref "U7") (pin "11") (pinfunction "TS_11") (pintype "passive"))
      (node (ref "U7") (pin "12") (pinfunction "RTRICk_12") (pintype "passive"))
      (node (ref "U7") (pin "17") (pinfunction "GND_17") (pintype "passive"))
      (node (ref "U7") (pin "7") (pinfunction "GND_7") (pintype "passive"))
      (node (ref "VBUS-") (pin "1") (pinfunction "1_1") (pintype "passive"))
      (node (ref "VD4") (pin "1") (pinfunction "A_1") (pintype "passive"))
      (node (ref "Vsys-") (pin "1") (pinfunction "1_1") (pintype "passive"))
      (node (ref "X1") (pin "2") (pinfunction "2_2") (pintype "passive"))
      (node (ref "X1") (pin "4") (pinfunction "4_4") (pintype "passive"))
    )
    (net (code "30") (name "Net-(C20-Pad2)") (class "Default")
      (node (ref "C20") (pin "2") (pinfunction "2_2") (pintype "passive"))
      (node (ref "R12") (pin "1") (pinfunction "1_1") (pintype "passive"))
    )
    (net (code "31") (name "Net-(C39-Pad2)") (class "Default")
      (node (ref "C39") (pin "2") (pinfunction "2_2") (pintype "passive"))
      (node (ref "R31") (pin "1") (pinfunction "1_1") (pintype "passive"))
    )
    (net (code "32") (name "Net-(C57-Pad2)") (class "Default")
      (node (ref "C57") (pin "2") (pinfunction "2_2") (pintype "passive"))
      (node (ref "R40") (pin "1") (pinfunction "1_1") (pintype "passive"))
    )
    (net (code "33") (name "Net-(CRG-A)") (class "Default")
      (node (ref "CRG") (pin "1") (pinfunction "A_1") (pintype "passive"))
      (node (ref "R42") (pin "2") (pinfunction "2_2") (pintype "passive"))
      (node (ref "STB") (pin "1") (pinfunction "A_1") (pintype "passive"))
    )
    (net (code "34") (name "Net-(CRG-K)") (class "Default")
      (node (ref "CRG") (pin "2") (pinfunction "K_2") (pintype "passive"))
      (node (ref "U7") (pin "15") (pinfunction "~CHRG_15") (pintype "passive"))
    )
    (net (code "35") (name "Net-(Q1-G)") (class "Default")
      (node (ref "C19") (pin "2") (pinfunction "2_2") (pintype "passive"))
      (node (ref "Q1") (pin "1") (pinfunction "G_1") (pintype "passive"))
      (node (ref "Q2") (pin "3") (pinfunction "C_3") (pintype "passive"))
      (node (ref "R7") (pin "2") (pinfunction "2_2") (pintype "passive"))
    )
    (net (code "36") (name "Net-(Q2-B)") (class "Default")
      (node (ref "Q2") (pin "1") (pinfunction "B_1") (pintype "passive"))
      (node (ref "R11") (pin "1") (pinfunction "1_1") (pintype "passive"))
      (node (ref "R14") (pin "2") (pinfunction "2_2") (pintype "passive"))
    )
    (net (code "37") (name "Net-(Q3-G)") (class "Default")
      (node (ref "C34") (pin "2") (pinfunction "2_2") (pintype "passive"))
      (node (ref "Q3") (pin "1") (pinfunction "G_1") (pintype "passive"))
      (node (ref "Q4") (pin "3") (pinfunction "C_3") (pintype "passive"))
      (node (ref "R16") (pin "2") (pinfunction "2_2") (pintype "passive"))
    )
    (net (code "38") (name "Net-(Q4-B)") (class "Default")
      (node (ref "Q4") (pin "1") (pinfunction "B_1") (pintype "passive"))
      (node (ref "R19") (pin "1") (pinfunction "1_1") (pintype "passive"))
      (node (ref "R25") (pin "2") (pinfunction "2_2") (pintype "passive"))
    )
    (net (code "39") (name "Net-(STB-K)") (class "Default")
      (node (ref "STB") (pin "2") (pinfunction "K_2") (pintype "passive"))
      (node (ref "U7") (pin "14") (pinfunction "~STDBY_14") (pintype "passive"))
    )
    (net (code "40") (name "Net-(U1-FB)") (class "Default")
      (node (ref "C17") (pin "1") (pinfunction "1_1") (pintype "passive"))
      (node (ref "R13") (pin "2") (pinfunction "2_2") (pintype "passive"))
      (node (ref "R9") (pin "1") (pinfunction "1_1") (pintype "passive"))
      (node (ref "U1") (pin "3") (pinfunction "FB_3") (pintype "passive"))
    )
    (net (code "41") (name "Net-(U1-SW)") (class "Default")
      (node (ref "C11") (pin "1") (pinfunction "1_1") (pintype "passive"))
      (node (ref "L1") (pin "2") (pinfunction "2_2") (pintype "passive"))
      (node (ref "U1") (pin "1") (pinfunction "SW_1") (pintype "passive"))
    )
    (net (code "42") (name "Net-(U2-BT1)") (class "Default")
      (node (ref "C22") (pin "1") (pinfunction "1_1") (pintype "passive"))
      (node (ref "U2") (pin "11") (pinfunction "BT1_11") (pintype "passive"))
    )
    (net (code "43") (name "Net-(U2-BT2)") (class "Default")
      (node (ref "C23") (pin "1") (pinfunction "1_1") (pintype "passive"))
      (node (ref "U2") (pin "14") (pinfunction "BT2_14") (pintype "passive"))
    )
    (net (code "44") (name "Net-(U2-COMP)") (class "Default")
      (node (ref "R12") (pin "2") (pinfunction "2_2") (pintype "passive"))
      (node (ref "U2") (pin "17") (pinfunction "COMP_17") (pintype "passive"))
    )
    (net (code "45") (name "Net-(U2-CSN)") (class "Default")
      (node (ref "5V") (pin "1") (pinfunction "1_1") (pintype "passive"))
      (node (ref "C10") (pin "1") (pinfunction "1_1") (pintype "passive"))
      (node (ref "C8") (pin "1") (pinfunction "1_1") (pintype "passive"))
      (node (ref "C9") (pin "1") (pinfunction "1_1") (pintype "passive"))
      (node (ref "R1") (pin "2") (pinfunction "2_2") (pintype "passive"))
      (node (ref "R6") (pin "1") (pinfunction "1_1") (pintype "passive"))
      (node (ref "U2") (pin "20") (pinfunction "CSN_20") (pintype "passive"))
    )
    (net (code "46") (name "Net-(U2-CSO)") (class "Default")
      (node (ref "R4") (pin "2") (pinfunction "2_2") (pintype "passive"))
      (node (ref "R5") (pin "1") (pinfunction "1_1") (pintype "passive"))
      (node (ref "U2") (pin "19") (pinfunction "CSO_19") (pintype "passive"))
    )
    (net (code "47") (name "Net-(U2-CSP)") (class "Default")
      (node (ref "C2") (pin "1") (pinfunction "1_1") (pintype "passive"))
      (node (ref "C7") (pin "1") (pinfunction "1_1") (pintype "passive"))
      (node (ref "R1") (pin "1") (pinfunction "1_1") (pintype "passive"))
      (node (ref "U2") (pin "1") (pinfunction "VOUT_1") (pintype "passive"))
      (node (ref "U2") (pin "21") (pinfunction "CSP_21") (pintype "passive"))
    )
    (net (code "48") (name "Net-(U2-FB)") (class "Default")
      (node (ref "R10") (pin "1") (pinfunction "1_1") (pintype "passive"))
      (node (ref "R6") (pin "2") (pinfunction "2_2") (pintype "passive"))
      (node (ref "U2") (pin "18") (pinfunction "FB_18") (pintype "passive"))
    )
    (net (code "49") (name "Net-(U2-SW1)") (class "Default")
      (node (ref "C22") (pin "2") (pinfunction "2_2") (pintype "passive"))
      (node (ref "L3") (pin "1") (pinfunction "1_1") (pintype "passive"))
      (node (ref "U2") (pin "12") (pinfunction "SW1_12") (pintype "passive"))
    )
    (net (code "50") (name "Net-(U2-SW2)") (class "Default")
      (node (ref "C23") (pin "2") (pinfunction "2_2") (pintype "passive"))
      (node (ref "L3") (pin "2") (pinfunction "2_2") (pintype "passive"))
      (node (ref "U2") (pin "13") (pinfunction "SW2_13") (pintype "passive"))
    )
    (net (code "51") (name "Net-(U2-VCC)") (class "Default")
      (node (ref "C18") (pin "1") (pinfunction "1_1") (pintype "passive"))
      (node (ref "R8") (pin "1") (pinfunction "1_1") (pintype "passive"))
      (node (ref "U2") (pin "9") (pinfunction "VCC_9") (pintype "passive"))
    )
    (net (code "52") (name "Net-(U2-VSET)") (class "Default")
      (node (ref "R8") (pin "2") (pinfunction "2_2") (pintype "passive"))
      (node (ref "U2") (pin "8") (pinfunction "VSET_8") (pintype "passive"))
    )
    (net (code "53") (name "Net-(U3-VCC)") (class "Default")
      (node (ref "Bead") (pin "2") (pinfunction "2_2") (pintype "passive"))
      (node (ref "C42") (pin "1") (pinfunction "1_1") (pintype "passive"))
      (node (ref "C63") (pin "1") (pinfunction "1_1") (pintype "passive"))
      (node (ref "U3") (pin "4") (pinfunction "VCC_4") (pintype "passive"))
    )
    (net (code "54") (name "Net-(U3-XTALI{slash}PB7)") (class "Default")
      (node (ref "C55") (pin "1") (pinfunction "1_1") (pintype "passive"))
      (node (ref "U3") (pin "8") (pinfunction "XTALI/PB7_8") (pintype "passive"))
      (node (ref "X1") (pin "3") (pinfunction "3_3") (pintype "passive"))
    )
    (net (code "55") (name "Net-(U3-XTALO{slash}PB6)") (class "Default")
      (node (ref "C54") (pin "1") (pinfunction "1_1") (pintype "passive"))
      (node (ref "U3") (pin "7") (pinfunction "XTALO/PB6_7") (pintype "passive"))
      (node (ref "X1") (pin "1") (pinfunction "1_1") (pintype "passive"))
    )
    (net (code "56") (name "Net-(U4-BT1)") (class "Default")
      (node (ref "C40") (pin "1") (pinfunction "1_1") (pintype "passive"))
      (node (ref "U4") (pin "11") (pinfunction "BT1_11") (pintype "passive"))
    )
    (net (code "57") (name "Net-(U4-BT2)") (class "Default")
      (node (ref "C41") (pin "1") (pinfunction "1_1") (pintype "passive"))
      (node (ref "U4") (pin "14") (pinfunction "BT2_14") (pintype "passive"))
    )
    (net (code "58") (name "Net-(U4-COMP)") (class "Default")
      (node (ref "R31") (pin "2") (pinfunction "2_2") (pintype "passive"))
      (node (ref "U4") (pin "17") (pinfunction "COMP_17") (pintype "passive"))
    )
    (net (code "59") (name "Net-(U4-CSN)") (class "Default")
      (node (ref "12V") (pin "1") (pinfunction "1_1") (pintype "passive"))
      (node (ref "C31") (pin "1") (pinfunction "1_1") (pintype "passive"))
      (node (ref "C32") (pin "1") (pinfunction "1_1") (pintype "passive"))
      (node (ref "C33") (pin "1") (pinfunction "1_1") (pintype "passive"))
      (node (ref "R15") (pin "2") (pinfunction "2_2") (pintype "passive"))
      (node (ref "R26") (pin "1") (pinfunction "1_1") (pintype "passive"))
      (node (ref "U4") (pin "20") (pinfunction "CSN_20") (pintype "passive"))
    )
    (net (code "60") (name "Net-(U4-CSO)") (class "Default")
      (node (ref "R24") (pin "2") (pinfunction "2_2") (pintype "passive"))
      (node (ref "R27") (pin "1") (pinfunction "1_1") (pintype "passive"))
      (node (ref "U4") (pin "19") (pinfunction "CSO_19") (pintype "passive"))
    )
    (net (code "61") (name "Net-(U4-CSP)") (class "Default")
      (node (ref "C24") (pin "1") (pinfunction "1_1") (pintype "passive"))
      (node (ref "C30") (pin "1") (pinfunction "1_1") (pintype "passive"))
      (node (ref "R15") (pin "1") (pinfunction "1_1") (pintype "passive"))
      (node (ref "U4") (pin "1") (pinfunction "VOUT_1") (pintype "passive"))
      (node (ref "U4") (pin "21") (pinfunction "CSP_21") (pintype "passive"))
    )
    (net (code "62") (name "Net-(U4-FB)") (class "Default")
      (node (ref "R26") (pin "2") (pinfunction "2_2") (pintype "passive"))
      (node (ref "R30") (pin "1") (pinfunction "1_1") (pintype "passive"))
      (node (ref "U4") (pin "18") (pinfunction "FB_18") (pintype "passive"))
    )
    (net (code "63") (name "Net-(U4-SW1)") (class "Default")
      (node (ref "C40") (pin "2") (pinfunction "2_2") (pintype "passive"))
      (node (ref "L4") (pin "1") (pinfunction "1_1") (pintype "passive"))
      (node (ref "U4") (pin "12") (pinfunction "SW1_12") (pintype "passive"))
    )
    (net (code "64") (name "Net-(U4-SW2)") (class "Default")
      (node (ref "C41") (pin "2") (pinfunction "2_2") (pintype "passive"))
      (node (ref "L4") (pin "2") (pinfunction "2_2") (pintype "passive"))
      (node (ref "U4") (pin "13") (pinfunction "SW2_13") (pintype "passive"))
    )
    (net (code "65") (name "Net-(U4-VCC)") (class "Default")
      (node (ref "C38") (pin "1") (pinfunction "1_1") (pintype "passive"))
      (node (ref "R29") (pin "1") (pinfunction "1_1") (pintype "passive"))
      (node (ref "U4") (pin "9") (pinfunction "VCC_9") (pintype "passive"))
    )
    (net (code "66") (name "Net-(U4-VSET)") (class "Default")
      (node (ref "R29") (pin "2") (pinfunction "2_2") (pintype "passive"))
      (node (ref "U4") (pin "8") (pinfunction "VSET_8") (pintype "passive"))
    )
    (net (code "67") (name "Net-(U5-BT1)") (class "Default")
      (node (ref "C58") (pin "1") (pinfunction "1_1") (pintype "passive"))
      (node (ref "U5") (pin "11") (pinfunction "BT1_11") (pintype "passive"))
    )
    (net (code "68") (name "Net-(U5-BT2)") (class "Default")
      (node (ref "C59") (pin "1") (pinfunction "1_1") (pintype "passive"))
      (node (ref "U5") (pin "14") (pinfunction "BT2_14") (pintype "passive"))
    )
    (net (code "69") (name "Net-(U5-COMP)") (class "Default")
      (node (ref "R40") (pin "2") (pinfunction "2_2") (pintype "passive"))
      (node (ref "U5") (pin "17") (pinfunction "COMP_17") (pintype "passive"))
    )
    (net (code "70") (name "Net-(U5-CSN)") (class "Default")
      (node (ref "15V") (pin "1") (pinfunction "1_1") (pintype "passive"))
      (node (ref "C50") (pin "1") (pinfunction "1_1") (pintype "passive"))
      (node (ref "C51") (pin "1") (pinfunction "1_1") (pintype "passive"))
      (node (ref "C52") (pin "1") (pinfunction "1_1") (pintype "passive"))
      (node (ref "R32") (pin "2") (pinfunction "2_2") (pintype "passive"))
      (node (ref "R37") (pin "1") (pinfunction "1_1") (pintype "passive"))
      (node (ref "U5") (pin "20") (pinfunction "CSN_20") (pintype "passive"))
    )
    (net (code "71") (name "Net-(U5-CSO)") (class "Default")
      (node (ref "R33") (pin "2") (pinfunction "2_2") (pintype "passive"))
      (node (ref "R36") (pin "1") (pinfunction "1_1") (pintype "passive"))
      (node (ref "U5") (pin "19") (pinfunction "CSO_19") (pintype "passive"))
    )
    (net (code "72") (name "Net-(U5-CSP)") (class "Default")
      (node (ref "C44") (pin "1") (pinfunction "1_1") (pintype "passive"))
      (node (ref "C49") (pin "1") (pinfunction "1_1") (pintype "passive"))
      (node (ref "R32") (pin "1") (pinfunction "1_1") (pintype "passive"))
      (node (ref "U5") (pin "1") (pinfunction "VOUT_1") (pintype "passive"))
      (node (ref "U5") (pin "21") (pinfunction "CSP_21") (pintype "passive"))
    )
    (net (code "73") (name "Net-(U5-FB)") (class "Default")
      (node (ref "R37") (pin "2") (pinfunction "2_2") (pintype "passive"))
      (node (ref "R39") (pin "1") (pinfunction "1_1") (pintype "passive"))
      (node (ref "U5") (pin "18") (pinfunction "FB_18") (pintype "passive"))
    )
    (net (code "74") (name "Net-(U5-SW1)") (class "Default")
      (node (ref "C58") (pin "2") (pinfunction "2_2") (pintype "passive"))
      (node (ref "L5") (pin "1") (pinfunction "1_1") (pintype "passive"))
      (node (ref "U5") (pin "12") (pinfunction "SW1_12") (pintype "passive"))
    )
    (net (code "75") (name "Net-(U5-SW2)") (class "Default")
      (node (ref "C59") (pin "2") (pinfunction "2_2") (pintype "passive"))
      (node (ref "L5") (pin "2") (pinfunction "2_2") (pintype "passive"))
      (node (ref "U5") (pin "13") (pinfunction "SW2_13") (pintype "passive"))
    )
    (net (code "76") (name "Net-(U5-VCC)") (class "Default")
      (node (ref "C56") (pin "1") (pinfunction "1_1") (pintype "passive"))
      (node (ref "R38") (pin "1") (pinfunction "1_1") (pintype "passive"))
      (node (ref "U5") (pin "9") (pinfunction "VCC_9") (pintype "passive"))
    )
    (net (code "77") (name "Net-(U5-VSET)") (class "Default")
      (node (ref "R38") (pin "2") (pinfunction "2_2") (pintype "passive"))
      (node (ref "U5") (pin "8") (pinfunction "VSET_8") (pintype "passive"))
    )
    (net (code "78") (name "Net-(U6-VDD)") (class "Default")
      (node (ref "C61") (pin "1") (pinfunction "1_1") (pintype "passive"))
      (node (ref "U6") (pin "1") (pinfunction "VDD_1") (pintype "passive"))
    )
    (net (code "79") (name "Net-(U7-CS)") (class "Default")
      (node (ref "C70") (pin "1") (pinfunction "1_1") (pintype "passive"))
      (node (ref "U7") (pin "10") (pinfunction "VREG_10") (pintype "passive"))
      (node (ref "U7") (pin "13") (pinfunction "CS_13") (pintype "passive"))
    )
    (net (code "80") (name "Net-(U7-VS)") (class "Default")
      (node (ref "C66") (pin "1") (pinfunction "1_1") (pintype "passive"))
      (node (ref "C67") (pin "1") (pinfunction "1_1") (pintype "passive"))
      (node (ref "L6") (pin "2") (pinfunction "2_2") (pintype "passive"))
      (node (ref "R41") (pin "1") (pinfunction "1_1") (pintype "passive"))
      (node (ref "U7") (pin "8") (pinfunction "VS_8") (pintype "passive"))
    )
    (net (code "81") (name "Net-(VD3-A)") (class "Default")
      (node (ref "C11") (pin "2") (pinfunction "2_2") (pintype "passive"))
      (node (ref "L2") (pin "2") (pinfunction "2_2") (pintype "passive"))
      (node (ref "VD3") (pin "1") (pinfunction "A_1") (pintype "passive"))
    )
    (net (code "82") (name "Net-(VD4-K)") (class "Default")
      (node (ref "L6") (pin "1") (pinfunction "1_1") (pintype "passive"))
      (node (ref "U7") (pin "2") (pinfunction "LX_2") (pintype "passive"))
      (node (ref "U7") (pin "3") (pinfunction "LX_3") (pintype "passive"))
      (node (ref "VD4") (pin "2") (pinfunction "K_2") (pintype "passive"))
    )
    (net (code "83") (name "unconnected-(D2-Pad3)") (class "Default")
      (node (ref "D2") (pin "3") (pintype "passive+no_connect"))
    )
    (net (code "84") (name "unconnected-(D3-Pad3)") (class "Default")
      (node (ref "D3") (pin "3") (pintype "passive+no_connect"))
    )
    (net (code "85") (name "unconnected-(D5-Pad3)") (class "Default")
      (node (ref "D5") (pin "3") (pintype "passive+no_connect"))
    )
    (net (code "86") (name "unconnected-(J1-A8_SBU1-Pad6)") (class "Default")
      (node (ref "J1") (pin "6") (pinfunction "A8_SBU1_6") (pintype "passive+no_connect"))
    )
    (net (code "87") (name "unconnected-(J1-B8_SBU2-Pad11)") (class "Default")
      (node (ref "J1") (pin "11") (pinfunction "B8_SBU2_11") (pintype "passive+no_connect"))
    )
    (net (code "88") (name "unconnected-(U1-NC-Pad6)") (class "Default")
      (node (ref "U1") (pin "6") (pinfunction "NC_6") (pintype "passive+no_connect"))
    )
    (net (code "89") (name "unconnected-(U2-NC-Pad7)") (class "Default")
      (node (ref "U2") (pin "7") (pinfunction "NC_7") (pintype "passive+no_connect"))
    )
    (net (code "90") (name "unconnected-(U2-NC-Pad10)") (class "Default")
      (node (ref "U2") (pin "10") (pinfunction "NC_10") (pintype "passive+no_connect"))
    )
    (net (code "91") (name "unconnected-(U2-NC-Pad15)") (class "Default")
      (node (ref "U2") (pin "15") (pinfunction "NC_15") (pintype "passive+no_connect"))
    )
    (net (code "92") (name "unconnected-(U3-A3-Pad26)") (class "Default")
      (node (ref "U3") (pin "26") (pinfunction "A3_26") (pintype "passive+no_connect"))
    )
    (net (code "93") (name "unconnected-(U3-A6-Pad19)") (class "Default")
      (node (ref "U3") (pin "19") (pinfunction "A6_19") (pintype "passive+no_connect"))
    )
    (net (code "94") (name "unconnected-(U3-AREF-Pad20)") (class "Default")
      (node (ref "U3") (pin "20") (pinfunction "AREF_20") (pintype "passive+no_connect"))
    )
    (net (code "95") (name "unconnected-(U3-D2-Pad32)") (class "Default")
      (node (ref "U3") (pin "32") (pinfunction "D2_32") (pintype "passive+no_connect"))
    )
    (net (code "96") (name "unconnected-(U3-PE3-Pad22)") (class "Default")
      (node (ref "U3") (pin "22") (pinfunction "PE3_22") (pintype "passive+no_connect"))
    )
    (net (code "97") (name "unconnected-(U3-PE4-Pad3)") (class "Default")
      (node (ref "U3") (pin "3") (pinfunction "PE4_3") (pintype "passive+no_connect"))
    )
    (net (code "98") (name "unconnected-(U3-PE5-Pad6)") (class "Default")
      (node (ref "U3") (pin "6") (pinfunction "PE5_6") (pintype "passive+no_connect"))
    )
    (net (code "99") (name "unconnected-(U3-SWC-Pad18)") (class "Default")
      (node (ref "U3") (pin "18") (pinfunction "SWC_18") (pintype "passive+no_connect"))
    )
    (net (code "100") (name "unconnected-(U3-SWD-Pad21)") (class "Default")
      (node (ref "U3") (pin "21") (pinfunction "SWD_21") (pintype "passive+no_connect"))
    )
    (net (code "101") (name "unconnected-(U4-NC-Pad7)") (class "Default")
      (node (ref "U4") (pin "7") (pinfunction "NC_7") (pintype "passive+no_connect"))
    )
    (net (code "102") (name "unconnected-(U4-NC-Pad10)") (class "Default")
      (node (ref "U4") (pin "10") (pinfunction "NC_10") (pintype "passive+no_connect"))
    )
    (net (code "103") (name "unconnected-(U4-NC-Pad15)") (class "Default")
      (node (ref "U4") (pin "15") (pinfunction "NC_15") (pintype "passive+no_connect"))
    )
    (net (code "104") (name "unconnected-(U5-NC-Pad7)") (class "Default")
      (node (ref "U5") (pin "7") (pinfunction "NC_7") (pintype "passive+no_connect"))
    )
    (net (code "105") (name "unconnected-(U5-NC-Pad10)") (class "Default")
      (node (ref "U5") (pin "10") (pinfunction "NC_10") (pintype "passive+no_connect"))
    )
    (net (code "106") (name "unconnected-(U5-NC-Pad15)") (class "Default")
      (node (ref "U5") (pin "15") (pinfunction "NC_15") (pintype "passive+no_connect"))
    )
    (net (code "107") (name "unconnected-(U6-CFG1-Pad9)") (class "Default")
      (node (ref "U6") (pin "9") (pinfunction "CFG1_9") (pintype "passive+no_connect"))
    )
    (net (code "108") (name "unconnected-(U6-CFG2-Pad2)") (class "Default")
      (node (ref "U6") (pin "2") (pinfunction "CFG2_2") (pintype "passive+no_connect"))
    )
    (net (code "109") (name "unconnected-(U6-CFG3-Pad3)") (class "Default")
      (node (ref "U6") (pin "3") (pinfunction "CFG3_3") (pintype "passive+no_connect"))
    )
    (net (code "110") (name "unconnected-(U6-PG-Pad10)") (class "Default")
      (node (ref "U6") (pin "10") (pinfunction "PG_10") (pintype "passive+no_connect"))
    )
    (net (code "111") (name "unconnected-(U7-PWR_ON-Pad6)") (class "Default")
      (node (ref "U7") (pin "6") (pinfunction "PWR_ON_6") (pintype "passive+no_connect"))
    )
  )
)
